# 2014-9-17.net
KiCad netlist of a schematic drawn in Altium Designer
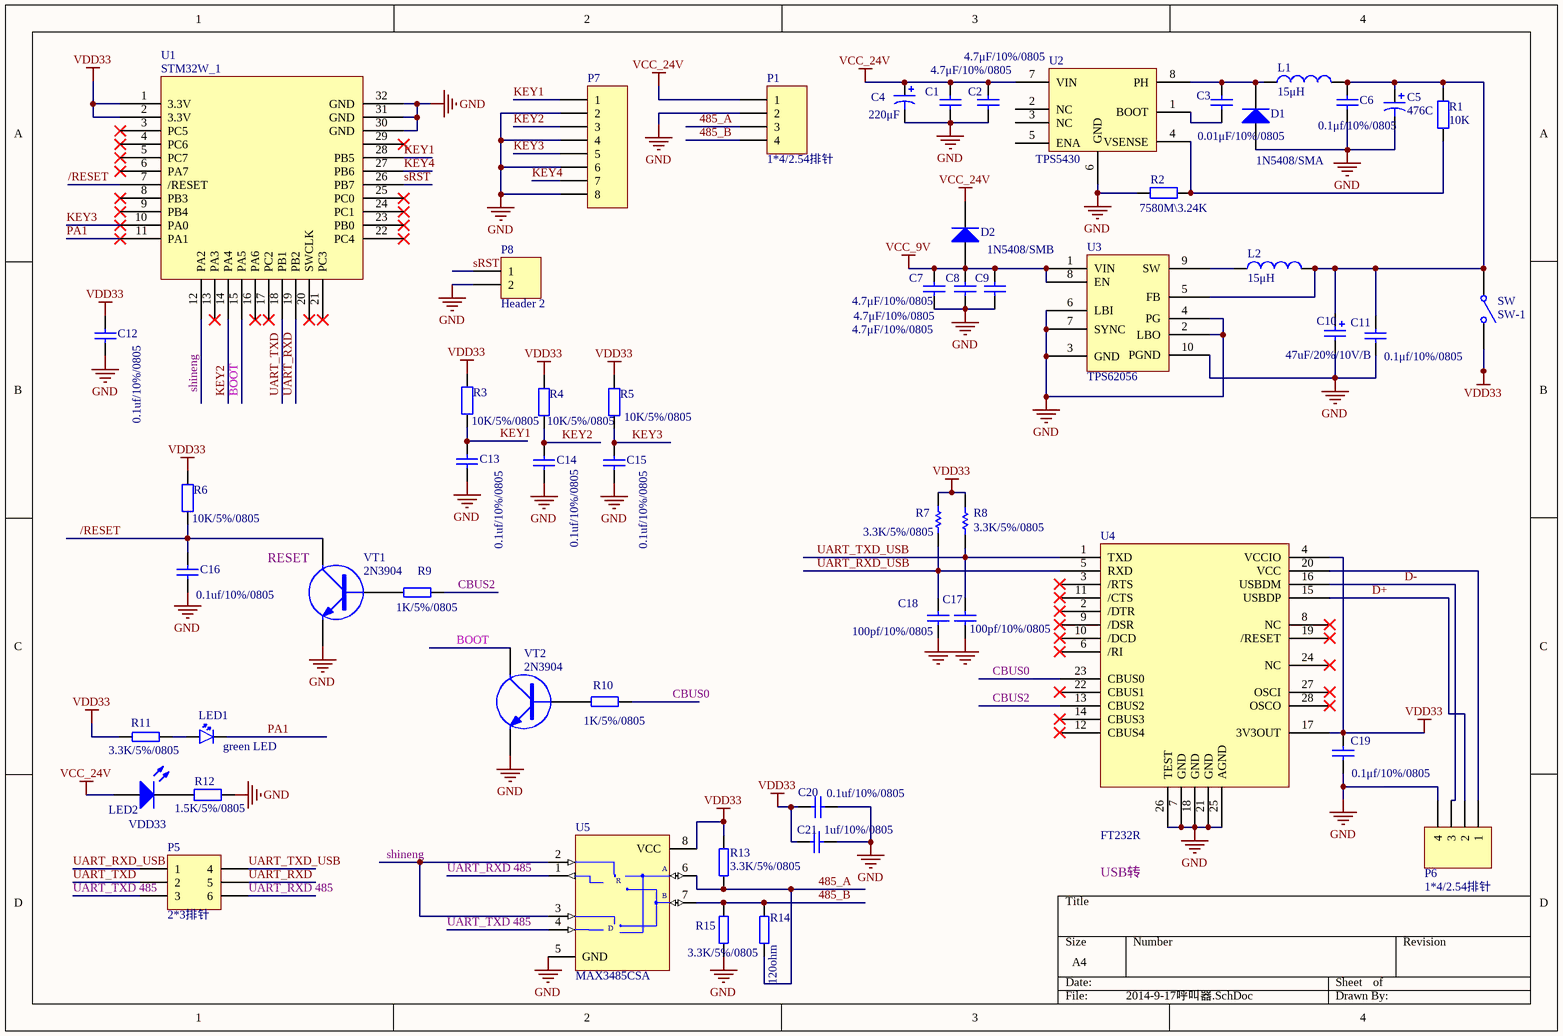
[diagram p0: 2014-9-17呼叫器.SchDoc]

(export (version "E")
  (design (tool "Eeschema 10.0.6"))
  (components
    (comp (ref "C1")
      (value "4.7μF/10%/0805")
      (footprint "C-0805")
      (description "Capacitor")
      (fields (field (name "PUBLISHER") "Altium Limited"))
      (libsource (lib "Miscellaneous Devices") (part "Cap"))
    )
    (comp (ref "C2")
      (value "4.7μF/10%/0805")
      (footprint "C-0805")
      (description "Capacitor")
      (fields (field (name "PUBLISHER") "Altium Limited"))
      (libsource (lib "Miscellaneous Devices") (part "Cap"))
    )
    (comp (ref "C3")
      (value "0.01μF/10%/0805")
      (footprint "C-0805")
      (description "Capacitor")
      (fields (field (name "PUBLISHER") "Altium Limited"))
      (libsource (lib "Miscellaneous Devices") (part "Cap"))
    )
    (comp (ref "C4")
      (value "220μF")
      (footprint "CZ3.0/6.5")
      (description "Polarized Capacitor (Radial)")
      (fields (field (name "PUBLISHER") "Altium Limited"))
      (libsource (lib "Miscellaneous Devices") (part "Cap Pol1"))
    )
    (comp (ref "C5")
      (value "476C")
      (footprint "C-TAN-D")
      (description "Polarized Capacitor (Radial)")
      (fields (field (name "PUBLISHER") "Altium Limited"))
      (libsource (lib "Miscellaneous Devices") (part "Cap Pol1"))
    )
    (comp (ref "C6")
      (value "0.1μf/10%/0805")
      (footprint "C-0805")
      (description "Capacitor")
      (fields (field (name "PUBLISHER") "Altium Limited"))
      (libsource (lib "Miscellaneous Devices") (part "Cap"))
    )
    (comp (ref "C7")
      (value "4.7μF/10%/0805")
      (footprint "C-0805")
      (description "Capacitor")
      (fields (field (name "PUBLISHER") "Altium Limited"))
      (libsource (lib "Miscellaneous Devices") (part "Cap"))
    )
    (comp (ref "C8")
      (value "4.7μF/10%/0805")
      (footprint "C-0805")
      (description "Capacitor")
      (fields (field (name "PUBLISHER") "Altium Limited"))
      (libsource (lib "Miscellaneous Devices") (part "Cap"))
    )
    (comp (ref "C9")
      (value "4.7μF/10%/0805")
      (footprint "C-0805")
      (description "Capacitor")
      (fields (field (name "PUBLISHER") "Altium Limited"))
      (libsource (lib "Miscellaneous Devices") (part "Cap"))
    )
    (comp (ref "C10")
      (value "47uF/20%/10V/B")
      (footprint "C-TAN-B")
      (libsource (lib "浙江关西电机数据库") (part "CAP_polarity"))
    )
    (comp (ref "C11")
      (value "0.1μf/10%/0805")
      (footprint "C-0805")
      (description "Capacitor")
      (fields (field (name "PUBLISHER") "Altium Limited"))
      (libsource (lib "Miscellaneous Devices") (part "Cap"))
    )
    (comp (ref "C12")
      (value "0.1uf/10%/0805")
      (footprint "C-0805")
      (description "Capacitor")
      (fields (field (name "PUBLISHER") "Altium Limited"))
      (libsource (lib "Miscellaneous Devices") (part "Cap"))
    )
    (comp (ref "C13")
      (value "0.1uf/10%/0805")
      (footprint "C-0805")
      (description "Capacitor")
      (fields (field (name "PUBLISHER") "Altium Limited"))
      (libsource (lib "Miscellaneous Devices") (part "Cap"))
    )
    (comp (ref "C14")
      (value "0.1uf/10%/0805")
      (footprint "C-0805")
      (description "Capacitor")
      (fields (field (name "PUBLISHER") "Altium Limited"))
      (libsource (lib "Miscellaneous Devices") (part "Cap"))
    )
    (comp (ref "C15")
      (value "0.1uf/10%/0805")
      (footprint "C-0805")
      (description "Capacitor")
      (fields (field (name "PUBLISHER") "Altium Limited"))
      (libsource (lib "Miscellaneous Devices") (part "Cap"))
    )
    (comp (ref "C16")
      (value "0.1uf/10%/0805")
      (footprint "C-0805")
      (description "Capacitor")
      (fields (field (name "PUBLISHER") "Altium Limited"))
      (libsource (lib "Miscellaneous Devices") (part "Cap"))
    )
    (comp (ref "C17")
      (value "100pf/10%/0805")
      (footprint "C-0805")
      (description "Capacitor")
      (fields (field (name "PUBLISHER") "Altium Limited"))
      (libsource (lib "Miscellaneous Devices") (part "Cap"))
    )
    (comp (ref "C18")
      (value "100pf/10%/0805")
      (footprint "C-0805")
      (description "Capacitor")
      (fields (field (name "PUBLISHER") "Altium Limited"))
      (libsource (lib "Miscellaneous Devices") (part "Cap"))
    )
    (comp (ref "C19")
      (value "0.1μf/10%/0805")
      (footprint "C-0805")
      (description "Capacitor")
      (fields (field (name "PUBLISHER") "Altium Limited"))
      (libsource (lib "Miscellaneous Devices") (part "Cap"))
    )
    (comp (ref "C20")
      (value "0.1uf/10%/0805")
      (footprint "C-0805")
      (description "Capacitor")
      (fields (field (name "PUBLISHER") "Altium Limited"))
      (libsource (lib "Miscellaneous Devices") (part "Cap"))
    )
    (comp (ref "C21")
      (value "1uf/10%/0805")
      (footprint "C-0805")
      (description "Capacitor")
      (fields (field (name "PUBLISHER") "Altium Limited"))
      (libsource (lib "Miscellaneous Devices") (part "Cap"))
    )
    (comp (ref "D1")
      (value "1N5408/SMA")
      (footprint "SMA 2+")
      (description "3 Amp Medium Power Silicon Rectifier Diode")
      (fields (field (name "PUBLISHER") "Altium Limited"))
      (libsource (lib "Miscellaneous Devices") (part "Diode 1N5408"))
    )
    (comp (ref "D2")
      (value "1N5408/SMB")
      (footprint "smb")
      (description "3 Amp Medium Power Silicon Rectifier Diode")
      (fields (field (name "PUBLISHER") "Altium Limited"))
      (libsource (lib "Miscellaneous Devices") (part "Diode 1N5408"))
    )
    (comp (ref "L1")
      (value "15μH")
      (footprint "GSDS104C2")
      (description "Inductor")
      (fields (field (name "PUBLISHER") "Altium Limited"))
      (libsource (lib "Miscellaneous Devices") (part "Inductor"))
    )
    (comp (ref "L2")
      (value "15μH")
      (footprint "GSDS104C2")
      (description "Inductor")
      (fields (field (name "PUBLISHER") "Altium Limited"))
      (libsource (lib "Miscellaneous Devices") (part "Inductor"))
    )
    (comp (ref "LED1") (value "green LED") (footprint "LED-φ3") (libsource (lib "Haze") (part "LED")))
    (comp (ref "LED2")
      (value "VDD33")
      (footprint "LED-φ3")
      (description "Typical BLUE SiC LED")
      (fields (field (name "PUBLISHER") "Altium Limited"))
      (libsource (lib "Miscellaneous Devices") (part "LED3"))
    )
    (comp (ref "P1")
      (value "1*4/2.54排针")
      (footprint "PIN-S-2.54-1*4")
      (description "Header, 4-Pin")
      (fields (field (name "PUBLISHER") "Altium Limited"))
      (libsource (lib "") (part "Header 4_1"))
    )
    (comp (ref "P5")
      (value "2*3排针")
      (footprint "HDR2X3_CEN")
      (description "Header, 3-Pin, Dual row")
      (fields (field (name "PUBLISHER") "Altium Limited"))
      (libsource (lib "Miscellaneous Connectors") (part "Header 3X2A"))
    )
    (comp (ref "P6")
      (value "1*4/2.54排针")
      (footprint "PIN-S-2.54-1*4")
      (description "Header, 4-Pin")
      (fields (field (name "PUBLISHER") "Altium Limited"))
      (libsource (lib "Miscellaneous Connectors") (part "Header 4"))
    )
    (comp (ref "P7")
      (value "Header 8")
      (footprint "HDR1X8")
      (description "Header, 8-Pin")
      (fields (field (name "PUBLISHER") "Altium Limited"))
      (libsource (lib "Miscellaneous Connectors") (part "Header 8"))
    )
    (comp (ref "P8")
      (value "Header 2")
      (footprint "HDR1X2")
      (description "Header, 2-Pin")
      (fields (field (name "PUBLISHER") "Altium Limited"))
      (libsource (lib "Miscellaneous Connectors") (part "Header 2"))
    )
    (comp (ref "R1")
      (value "10K")
      (footprint "R-0805")
      (description "Resistor")
      (fields (field (name "PUBLISHER") "Altium Limited"))
      (libsource (lib "Miscellaneous Devices") (part "Res2"))
    )
    (comp (ref "R2")
      (value "7580~{M}3.24K")
      (footprint "R-0805")
      (description "Resistor")
      (fields (field (name "PUBLISHER") "Altium Limited"))
      (libsource (lib "") (part "Res2_1"))
    )
    (comp (ref "R3")
      (value "10K/5%/0805")
      (footprint "R-0805")
      (description "Resistor")
      (fields (field (name "PUBLISHER") "Altium Limited"))
      (libsource (lib "Miscellaneous Devices") (part "Res2"))
    )
    (comp (ref "R4")
      (value "10K/5%/0805")
      (footprint "R-0805")
      (description "Resistor")
      (fields (field (name "PUBLISHER") "Altium Limited"))
      (libsource (lib "Miscellaneous Devices") (part "Res2"))
    )
    (comp (ref "R5")
      (value "10K/5%/0805")
      (footprint "R-0805")
      (description "Resistor")
      (fields (field (name "PUBLISHER") "Altium Limited"))
      (libsource (lib "Miscellaneous Devices") (part "Res2"))
    )
    (comp (ref "R6")
      (value "10K/5%/0805")
      (footprint "R-0805")
      (description "Resistor")
      (fields (field (name "PUBLISHER") "Altium Limited"))
      (libsource (lib "Miscellaneous Devices") (part "Res2"))
    )
    (comp (ref "R7")
      (value "3.3K/5%/0805")
      (footprint "R-0805")
      (libsource (lib "SCHLIBRARIES") (part "RES_1"))
    )
    (comp (ref "R8")
      (value "3.3K/5%/0805")
      (footprint "R-0805")
      (libsource (lib "SCHLIBRARIES") (part "RES_1"))
    )
    (comp (ref "R9")
      (value "1K/5%/0805")
      (footprint "R-0805")
      (description "R")
      (libsource (lib "Haze") (part "RES"))
    )
    (comp (ref "R10")
      (value "1K/5%/0805")
      (footprint "R-0805")
      (description "R")
      (libsource (lib "Haze") (part "RES"))
    )
    (comp (ref "R11")
      (value "3.3K/5%/0805")
      (footprint "R-0805")
      (description "R")
      (libsource (lib "Haze") (part "RES"))
    )
    (comp (ref "R12")
      (value "1.5K/5%/0805")
      (footprint "R-0805")
      (description "Resistor")
      (fields (field (name "PUBLISHER") "Altium Limited"))
      (libsource (lib "") (part "Res2_1"))
    )
    (comp (ref "R13")
      (value "3.3K/5%/0805")
      (footprint "R-0805")
      (description "R")
      (libsource (lib "Haze") (part "RES"))
    )
    (comp (ref "R14")
      (value "120ohm")
      (footprint "R-0805")
      (description "R")
      (libsource (lib "Haze") (part "RES"))
    )
    (comp (ref "R15")
      (value "3.3K/5%/0805")
      (footprint "R-0805")
      (description "R")
      (libsource (lib "Haze") (part "RES"))
    )
    (comp (ref "SW")
      (value "SW-1")
      (footprint "PIN-S-2.54-1*2")
      (libsource (lib "SCHLIBRARIES") (part "SW-1"))
    )
    (comp (ref "U1")
      (value "STM32W_1")
      (footprint "STM32W108-3")
      (libsource (lib "STM32W108-3") (part "STM32W108-3"))
    )
    (comp (ref "U2") (value "TPS5430") (footprint "SO-G8") (libsource (lib "SCHLIBRARIES") (part "TPS5430")))
    (comp (ref "U3")
      (value "TPS62056")
      (footprint "MSOP-10")
      (libsource (lib "SCHLIBRARIES") (part "TPS62056"))
    )
    (comp (ref "U4") (value "FT232R") (footprint "SSOP-28") (libsource (lib "Haze") (part "FT232R")))
    (comp (ref "U5")
      (value "MAX3485CSA")
      (footprint "SO-G8")
      (description "Low-Power, Slew-Rate-Limited RS-485/RS-422 Transceiver")
      (fields (field (name "PUBLISHER") "Altium Limited"))
      (libsource (lib "Maxim Communication Transceiver") (part "MAX485CSA"))
    )
    (comp (ref "VT1")
      (value "2N3904")
      (footprint "SOT23-3")
      (description "NPN Transistor")
      (libsource (lib "Haze") (part "NPN"))
    )
    (comp (ref "VT2")
      (value "2N3904")
      (footprint "SOT23-3")
      (description "NPN Transistor")
      (libsource (lib "Haze") (part "NPN"))
    )
  )
  (nets
    (net (code "1") (name "/485_A") (class "Default")
      (node (ref "P1") (pin "3") (pinfunction "3_3") (pintype "passive"))
      (node (ref "R13") (pin "1") (pinfunction "1_1") (pintype "passive"))
      (node (ref "R14") (pin "2") (pinfunction "2_2") (pintype "passive"))
      (node (ref "U5") (pin "6") (pinfunction "A_6") (pintype "bidirectional"))
    )
    (net (code "2") (name "/485_B") (class "Default")
      (node (ref "P1") (pin "4") (pinfunction "4_4") (pintype "passive"))
      (node (ref "R14") (pin "1") (pinfunction "1_1") (pintype "passive"))
      (node (ref "R15") (pin "2") (pinfunction "2_2") (pintype "passive"))
      (node (ref "U5") (pin "7") (pinfunction "B_7") (pintype "bidirectional"))
    )
    (net (code "3") (name "/BOOT") (class "Default")
      (node (ref "U1") (pin "15") (pinfunction "PA5_15") (pintype "passive"))
      (node (ref "VT2") (pin "3") (pinfunction "C_3") (pintype "passive"))
    )
    (net (code "4") (name "/CBUS0") (class "Default")
      (node (ref "R10") (pin "2") (pinfunction "2_2") (pintype "passive"))
      (node (ref "U4") (pin "23") (pinfunction "CBUS0_23") (pintype "passive"))
    )
    (net (code "5") (name "/CBUS2") (class "Default")
      (node (ref "R9") (pin "2") (pinfunction "2_2") (pintype "passive"))
      (node (ref "U4") (pin "13") (pinfunction "CBUS2_13") (pintype "passive"))
    )
    (net (code "6") (name "/D+") (class "Default")
      (node (ref "P6") (pin "2") (pinfunction "2_2") (pintype "passive"))
      (node (ref "U4") (pin "15") (pinfunction "USBDP_15") (pintype "passive"))
    )
    (net (code "7") (name "/D-") (class "Default")
      (node (ref "P6") (pin "3") (pinfunction "3_3") (pintype "passive"))
      (node (ref "U4") (pin "16") (pinfunction "USBDM_16") (pintype "passive"))
    )
    (net (code "8") (name "/KEY1") (class "Default")
      (node (ref "C13") (pin "2") (pinfunction "2_2") (pintype "passive"))
      (node (ref "P7") (pin "1") (pinfunction "1_1") (pintype "passive"))
      (node (ref "R3") (pin "1") (pinfunction "1_1") (pintype "passive"))
      (node (ref "U1") (pin "28") (pinfunction "PB5_28") (pintype "passive"))
    )
    (net (code "9") (name "/KEY2") (class "Default")
      (node (ref "C14") (pin "2") (pinfunction "2_2") (pintype "passive"))
      (node (ref "P7") (pin "3") (pinfunction "3_3") (pintype "passive"))
      (node (ref "R4") (pin "1") (pinfunction "1_1") (pintype "passive"))
      (node (ref "U1") (pin "14") (pinfunction "PA4_14") (pintype "passive"))
    )
    (net (code "10") (name "/KEY3") (class "Default")
      (node (ref "C15") (pin "2") (pinfunction "2_2") (pintype "passive"))
      (node (ref "P7") (pin "5") (pinfunction "5_5") (pintype "passive"))
      (node (ref "R5") (pin "1") (pinfunction "1_1") (pintype "passive"))
      (node (ref "U1") (pin "10") (pinfunction "PA0_10") (pintype "passive"))
    )
    (net (code "11") (name "/KEY4") (class "Default")
      (node (ref "P7") (pin "7") (pinfunction "7_7") (pintype "passive"))
      (node (ref "U1") (pin "27") (pinfunction "PB6_27") (pintype "passive"))
    )
    (net (code "12") (name "/PA1") (class "Default")
      (node (ref "LED1") (pin "2") (pinfunction "K_2") (pintype "passive"))
      (node (ref "U1") (pin "11") (pinfunction "PA1_11") (pintype "passive"))
    )
    (net (code "13") (name "/UART_RXD") (class "Default")
      (node (ref "P5") (pin "5") (pinfunction "5_5") (pintype "passive"))
      (node (ref "U1") (pin "19") (pinfunction "PB2_19") (pintype "passive"))
    )
    (net (code "14") (name "/UART_RXD 485") (class "Default")
      (node (ref "P5") (pin "6") (pinfunction "6_6") (pintype "passive"))
      (node (ref "U5") (pin "1") (pinfunction "RO_1") (pintype "output"))
    )
    (net (code "15") (name "/UART_RXD_USB") (class "Default")
      (node (ref "C18") (pin "2") (pinfunction "2_2") (pintype "passive"))
      (node (ref "P5") (pin "1") (pinfunction "1_1") (pintype "passive"))
      (node (ref "R7") (pin "1") (pinfunction "1_1") (pintype "passive"))
      (node (ref "U4") (pin "5") (pinfunction "RXD_5") (pintype "passive"))
    )
    (net (code "16") (name "/UART_TXD") (class "Default")
      (node (ref "P5") (pin "2") (pinfunction "2_2") (pintype "passive"))
      (node (ref "U1") (pin "18") (pinfunction "PB1_18") (pintype "passive"))
    )
    (net (code "17") (name "/UART_TXD 485") (class "Default")
      (node (ref "P5") (pin "3") (pinfunction "3_3") (pintype "passive"))
      (node (ref "U5") (pin "4") (pinfunction "DI_4") (pintype "input"))
    )
    (net (code "18") (name "/UART_TXD_USB") (class "Default")
      (node (ref "C17") (pin "2") (pinfunction "2_2") (pintype "passive"))
      (node (ref "P5") (pin "4") (pinfunction "4_4") (pintype "passive"))
      (node (ref "R8") (pin "1") (pinfunction "1_1") (pintype "passive"))
      (node (ref "U4") (pin "1") (pinfunction "TXD_1") (pintype "passive"))
    )
    (net (code "19") (name "/sRST") (class "Default")
      (node (ref "P8") (pin "1") (pinfunction "1_1") (pintype "passive"))
      (node (ref "U1") (pin "26") (pinfunction "PB7_26") (pintype "passive"))
    )
    (net (code "20") (name "/shineng") (class "Default")
      (node (ref "U1") (pin "12") (pinfunction "PA2_12") (pintype "passive"))
      (node (ref "U5") (pin "2") (pinfunction "~{RE}_2") (pintype "input"))
      (node (ref "U5") (pin "3") (pinfunction "DE_3") (pintype "input"))
    )
    (net (code "21") (name "/{slash}RESET") (class "Default")
      (node (ref "C16") (pin "2") (pinfunction "2_2") (pintype "passive"))
      (node (ref "R6") (pin "1") (pinfunction "1_1") (pintype "passive"))
      (node (ref "U1") (pin "7") (pinfunction "/RESET_7") (pintype "passive"))
      (node (ref "VT1") (pin "3") (pinfunction "C_3") (pintype "passive"))
    )
    (net (code "22") (name "GND") (class "Default")
      (node (ref "C1") (pin "1") (pinfunction "1_1") (pintype "passive"))
      (node (ref "C10") (pin "2") (pinfunction "2_2") (pintype "passive"))
      (node (ref "C11") (pin "1") (pinfunction "1_1") (pintype "passive"))
      (node (ref "C12") (pin "1") (pinfunction "1_1") (pintype "passive"))
      (node (ref "C13") (pin "1") (pinfunction "1_1") (pintype "passive"))
      (node (ref "C14") (pin "1") (pinfunction "1_1") (pintype "passive"))
      (node (ref "C15") (pin "1") (pinfunction "1_1") (pintype "passive"))
      (node (ref "C16") (pin "1") (pinfunction "1_1") (pintype "passive"))
      (node (ref "C17") (pin "1") (pinfunction "1_1") (pintype "passive"))
      (node (ref "C18") (pin "1") (pinfunction "1_1") (pintype "passive"))
      (node (ref "C19") (pin "1") (pinfunction "1_1") (pintype "passive"))
      (node (ref "C2") (pin "1") (pinfunction "1_1") (pintype "passive"))
      (node (ref "C20") (pin "1") (pinfunction "1_1") (pintype "passive"))
      (node (ref "C21") (pin "1") (pinfunction "1_1") (pintype "passive"))
      (node (ref "C4") (pin "2") (pinfunction "2_2") (pintype "passive"))
      (node (ref "C5") (pin "2") (pinfunction "2_2") (pintype "passive"))
      (node (ref "C6") (pin "1") (pinfunction "1_1") (pintype "passive"))
      (node (ref "C7") (pin "1") (pinfunction "1_1") (pintype "passive"))
      (node (ref "C8") (pin "1") (pinfunction "1_1") (pintype "passive"))
      (node (ref "C9") (pin "1") (pinfunction "1_1") (pintype "passive"))
      (node (ref "D1") (pin "1") (pinfunction "A_1") (pintype "passive"))
      (node (ref "P1") (pin "2") (pinfunction "2_2") (pintype "passive"))
      (node (ref "P6") (pin "4") (pinfunction "4_4") (pintype "passive"))
      (node (ref "P7") (pin "2") (pinfunction "2_2") (pintype "passive"))
      (node (ref "P7") (pin "4") (pinfunction "4_4") (pintype "passive"))
      (node (ref "P7") (pin "6") (pinfunction "6_6") (pintype "passive"))
      (node (ref "P7") (pin "8") (pinfunction "8_8") (pintype "passive"))
      (node (ref "P8") (pin "2") (pinfunction "2_2") (pintype "passive"))
      (node (ref "R12") (pin "1") (pinfunction "1_1") (pintype "passive"))
      (node (ref "R15") (pin "1") (pinfunction "1_1") (pintype "passive"))
      (node (ref "R2") (pin "2") (pinfunction "2_2") (pintype "passive"))
      (node (ref "U1") (pin "30") (pinfunction "GND_30") (pintype "passive"))
      (node (ref "U1") (pin "31") (pinfunction "GND_31") (pintype "passive"))
      (node (ref "U1") (pin "32") (pinfunction "GND_32") (pintype "passive"))
      (node (ref "U2") (pin "6") (pinfunction "GND_6") (pintype "passive"))
      (node (ref "U3") (pin "10") (pinfunction "PGND_10") (pintype "passive"))
      (node (ref "U3") (pin "2") (pinfunction "LBO_2") (pintype "passive"))
      (node (ref "U3") (pin "3") (pinfunction "GND_3") (pintype "passive"))
      (node (ref "U3") (pin "4") (pinfunction "PG_4") (pintype "passive"))
      (node (ref "U3") (pin "6") (pinfunction "LBI_6") (pintype "passive"))
      (node (ref "U3") (pin "7") (pinfunction "SYNC_7") (pintype "passive"))
      (node (ref "U4") (pin "18") (pinfunction "GND_18") (pintype "passive"))
      (node (ref "U4") (pin "21") (pinfunction "GND_21") (pintype "passive"))
      (node (ref "U4") (pin "25") (pinfunction "AGND_25") (pintype "passive"))
      (node (ref "U4") (pin "26") (pinfunction "TEST_26") (pintype "passive"))
      (node (ref "U4") (pin "7") (pinfunction "GND_7") (pintype "passive"))
      (node (ref "U5") (pin "5") (pinfunction "GND_5") (pintype "power_in"))
      (node (ref "VT1") (pin "2") (pinfunction "E_2") (pintype "passive"))
      (node (ref "VT2") (pin "2") (pinfunction "E_2") (pintype "passive"))
    )
    (net (code "23") (name "Net-(D1-K)") (class "Default")
      (node (ref "C3") (pin "2") (pinfunction "2_2") (pintype "passive"))
      (node (ref "D1") (pin "2") (pinfunction "K_2") (pintype "passive"))
      (node (ref "L1") (pin "1") (pinfunction "1_1") (pintype "passive"))
      (node (ref "U2") (pin "8") (pinfunction "PH_8") (pintype "passive"))
    )
    (net (code "24") (name "Net-(LED1-A)") (class "Default")
      (node (ref "LED1") (pin "1") (pinfunction "A_1") (pintype "passive"))
      (node (ref "R11") (pin "2") (pinfunction "2_2") (pintype "passive"))
    )
    (net (code "25") (name "Net-(LED2-K)") (class "Default")
      (node (ref "LED2") (pin "2") (pinfunction "K_2") (pintype "passive"))
      (node (ref "R12") (pin "2") (pinfunction "2_2") (pintype "passive"))
    )
    (net (code "26") (name "Net-(U2-BOOT)") (class "Default")
      (node (ref "C3") (pin "1") (pinfunction "1_1") (pintype "passive"))
      (node (ref "U2") (pin "1") (pinfunction "BOOT_1") (pintype "passive"))
    )
    (net (code "27") (name "Net-(U2-VSENSE)") (class "Default")
      (node (ref "R1") (pin "1") (pinfunction "1_1") (pintype "passive"))
      (node (ref "R2") (pin "1") (pinfunction "1_1") (pintype "passive"))
      (node (ref "U2") (pin "4") (pinfunction "VSENSE_4") (pintype "passive"))
    )
    (net (code "28") (name "Net-(U3-FB)") (class "Default")
      (node (ref "C10") (pin "1") (pinfunction "1_1") (pintype "passive"))
      (node (ref "C11") (pin "2") (pinfunction "2_2") (pintype "passive"))
      (node (ref "C5") (pin "1") (pinfunction "1_1") (pintype "passive"))
      (node (ref "C6") (pin "2") (pinfunction "2_2") (pintype "passive"))
      (node (ref "L1") (pin "2") (pinfunction "2_2") (pintype "passive"))
      (node (ref "L2") (pin "2") (pinfunction "2_2") (pintype "passive"))
      (node (ref "R1") (pin "2") (pinfunction "2_2") (pintype "passive"))
      (node (ref "SW") (pin "1") (pinfunction "1_1") (pintype "passive"))
      (node (ref "U3") (pin "5") (pinfunction "FB_5") (pintype "passive"))
    )
    (net (code "29") (name "Net-(U3-SW)") (class "Default")
      (node (ref "L2") (pin "1") (pinfunction "1_1") (pintype "passive"))
      (node (ref "U3") (pin "9") (pinfunction "SW_9") (pintype "passive"))
    )
    (net (code "30") (name "Net-(U4-VCC)") (class "Default")
      (node (ref "P6") (pin "1") (pinfunction "1_1") (pintype "passive"))
      (node (ref "U4") (pin "20") (pinfunction "VCC_20") (pintype "passive"))
    )
    (net (code "31") (name "Net-(VT1-B)") (class "Default")
      (node (ref "R9") (pin "1") (pinfunction "1_1") (pintype "passive"))
      (node (ref "VT1") (pin "1") (pinfunction "B_1") (pintype "passive"))
    )
    (net (code "32") (name "Net-(VT2-B)") (class "Default")
      (node (ref "R10") (pin "1") (pinfunction "1_1") (pintype "passive"))
      (node (ref "VT2") (pin "1") (pinfunction "B_1") (pintype "passive"))
    )
    (net (code "33") (name "VCC_9V") (class "Default")
      (node (ref "C7") (pin "2") (pinfunction "2_2") (pintype "passive"))
      (node (ref "C8") (pin "2") (pinfunction "2_2") (pintype "passive"))
      (node (ref "C9") (pin "2") (pinfunction "2_2") (pintype "passive"))
      (node (ref "D2") (pin "1") (pinfunction "A_1") (pintype "passive"))
      (node (ref "U3") (pin "1") (pinfunction "VIN_1") (pintype "passive"))
      (node (ref "U3") (pin "8") (pinfunction "EN_8") (pintype "passive"))
    )
    (net (code "34") (name "VCC_24V") (class "Default")
      (node (ref "C1") (pin "2") (pinfunction "2_2") (pintype "passive"))
      (node (ref "C2") (pin "2") (pinfunction "2_2") (pintype "passive"))
      (node (ref "C4") (pin "1") (pinfunction "1_1") (pintype "passive"))
      (node (ref "D2") (pin "2") (pinfunction "K_2") (pintype "passive"))
      (node (ref "LED2") (pin "1") (pinfunction "A_1") (pintype "passive"))
      (node (ref "P1") (pin "1") (pinfunction "1_1") (pintype "passive"))
      (node (ref "U2") (pin "7") (pinfunction "VIN_7") (pintype "passive"))
    )
    (net (code "35") (name "VDD33") (class "Default")
      (node (ref "C12") (pin "2") (pinfunction "2_2") (pintype "passive"))
      (node (ref "C19") (pin "2") (pinfunction "2_2") (pintype "passive"))
      (node (ref "C20") (pin "2") (pinfunction "2_2") (pintype "passive"))
      (node (ref "C21") (pin "2") (pinfunction "2_2") (pintype "passive"))
      (node (ref "R11") (pin "1") (pinfunction "1_1") (pintype "passive"))
      (node (ref "R13") (pin "2") (pinfunction "2_2") (pintype "passive"))
      (node (ref "R3") (pin "2") (pinfunction "2_2") (pintype "passive"))
      (node (ref "R4") (pin "2") (pinfunction "2_2") (pintype "passive"))
      (node (ref "R5") (pin "2") (pinfunction "2_2") (pintype "passive"))
      (node (ref "R6") (pin "2") (pinfunction "2_2") (pintype "passive"))
      (node (ref "R7") (pin "2") (pinfunction "2_2") (pintype "passive"))
      (node (ref "R8") (pin "2") (pinfunction "2_2") (pintype "passive"))
      (node (ref "SW") (pin "2") (pinfunction "2_2") (pintype "passive"))
      (node (ref "U1") (pin "1") (pinfunction "3.3V_1") (pintype "passive"))
      (node (ref "U1") (pin "2") (pinfunction "3.3V_2") (pintype "passive"))
      (node (ref "U4") (pin "17") (pinfunction "3V3OUT_17") (pintype "passive"))
      (node (ref "U4") (pin "4") (pinfunction "VCCIO_4") (pintype "passive"))
      (node (ref "U5") (pin "8") (pinfunction "VCC_8") (pintype "power_in"))
    )
    (net (code "36") (name "unconnected-(U1-PA3-Pad13)") (class "Default")
      (node (ref "U1") (pin "13") (pinfunction "PA3_13") (pintype "passive+no_connect"))
    )
    (net (code "37") (name "unconnected-(U1-PA6-Pad16)") (class "Default")
      (node (ref "U1") (pin "16") (pinfunction "PA6_16") (pintype "passive+no_connect"))
    )
    (net (code "38") (name "unconnected-(U1-PA7-Pad6)") (class "Default")
      (node (ref "U1") (pin "6") (pinfunction "PA7_6") (pintype "passive+no_connect"))
    )
    (net (code "39") (name "unconnected-(U1-PB0-Pad23)") (class "Default")
      (node (ref "U1") (pin "23") (pinfunction "PB0_23") (pintype "passive+no_connect"))
    )
    (net (code "40") (name "unconnected-(U1-PB3-Pad8)") (class "Default")
      (node (ref "U1") (pin "8") (pinfunction "PB3_8") (pintype "passive+no_connect"))
    )
    (net (code "41") (name "unconnected-(U1-PB4-Pad9)") (class "Default")
      (node (ref "U1") (pin "9") (pinfunction "PB4_9") (pintype "passive+no_connect"))
    )
    (net (code "42") (name "unconnected-(U1-PC0-Pad25)") (class "Default")
      (node (ref "U1") (pin "25") (pinfunction "PC0_25") (pintype "passive+no_connect"))
    )
    (net (code "43") (name "unconnected-(U1-PC1-Pad24)") (class "Default")
      (node (ref "U1") (pin "24") (pinfunction "PC1_24") (pintype "passive+no_connect"))
    )
    (net (code "44") (name "unconnected-(U1-PC2-Pad17)") (class "Default")
      (node (ref "U1") (pin "17") (pinfunction "PC2_17") (pintype "passive+no_connect"))
    )
    (net (code "45") (name "unconnected-(U1-PC3-Pad21)") (class "Default")
      (node (ref "U1") (pin "21") (pinfunction "PC3_21") (pintype "passive+no_connect"))
    )
    (net (code "46") (name "unconnected-(U1-PC4-Pad22)") (class "Default")
      (node (ref "U1") (pin "22") (pinfunction "PC4_22") (pintype "passive+no_connect"))
    )
    (net (code "47") (name "unconnected-(U1-PC5-Pad3)") (class "Default")
      (node (ref "U1") (pin "3") (pinfunction "PC5_3") (pintype "passive+no_connect"))
    )
    (net (code "48") (name "unconnected-(U1-PC6-Pad4)") (class "Default")
      (node (ref "U1") (pin "4") (pinfunction "PC6_4") (pintype "passive+no_connect"))
    )
    (net (code "49") (name "unconnected-(U1-PC7-Pad5)") (class "Default")
      (node (ref "U1") (pin "5") (pinfunction "PC7_5") (pintype "passive+no_connect"))
    )
    (net (code "50") (name "unconnected-(U1-Pad29)") (class "Default")
      (node (ref "U1") (pin "29") (pintype "passive+no_connect"))
    )
    (net (code "51") (name "unconnected-(U1-SWCLK-Pad20)") (class "Default")
      (node (ref "U1") (pin "20") (pinfunction "SWCLK_20") (pintype "passive+no_connect"))
    )
    (net (code "52") (name "unconnected-(U2-ENA-Pad5)") (class "Default")
      (node (ref "U2") (pin "5") (pinfunction "ENA_5") (pintype "passive"))
    )
    (net (code "53") (name "unconnected-(U2-NC-Pad2)") (class "Default")
      (node (ref "U2") (pin "2") (pinfunction "NC_2") (pintype "passive"))
    )
    (net (code "54") (name "unconnected-(U2-NC-Pad3)") (class "Default")
      (node (ref "U2") (pin "3") (pinfunction "NC_3") (pintype "passive"))
    )
    (net (code "55") (name "unconnected-(U4-CBUS1-Pad22)") (class "Default")
      (node (ref "U4") (pin "22") (pinfunction "CBUS1_22") (pintype "passive+no_connect"))
    )
    (net (code "56") (name "unconnected-(U4-CBUS3-Pad14)") (class "Default")
      (node (ref "U4") (pin "14") (pinfunction "CBUS3_14") (pintype "passive+no_connect"))
    )
    (net (code "57") (name "unconnected-(U4-CBUS4-Pad12)") (class "Default")
      (node (ref "U4") (pin "12") (pinfunction "CBUS4_12") (pintype "passive+no_connect"))
    )
    (net (code "58") (name "unconnected-(U4-NC-Pad8)") (class "Default")
      (node (ref "U4") (pin "8") (pinfunction "NC_8") (pintype "passive+no_connect"))
    )
    (net (code "59") (name "unconnected-(U4-NC-Pad24)") (class "Default")
      (node (ref "U4") (pin "24") (pinfunction "NC_24") (pintype "passive+no_connect"))
    )
    (net (code "60") (name "unconnected-(U4-OSCI-Pad27)") (class "Default")
      (node (ref "U4") (pin "27") (pinfunction "OSCI_27") (pintype "passive+no_connect"))
    )
    (net (code "61") (name "unconnected-(U4-OSCO-Pad28)") (class "Default")
      (node (ref "U4") (pin "28") (pinfunction "OSCO_28") (pintype "passive+no_connect"))
    )
    (net (code "62") (name "unconnected-(U4-{slash}CTS-Pad11)") (class "Default")
      (node (ref "U4") (pin "11") (pinfunction "/CTS_11") (pintype "passive+no_connect"))
    )
    (net (code "63") (name "unconnected-(U4-{slash}DCD-Pad10)") (class "Default")
      (node (ref "U4") (pin "10") (pinfunction "/DCD_10") (pintype "passive+no_connect"))
    )
    (net (code "64") (name "unconnected-(U4-{slash}DSR-Pad9)") (class "Default")
      (node (ref "U4") (pin "9") (pinfunction "/DSR_9") (pintype "passive+no_connect"))
    )
    (net (code "65") (name "unconnected-(U4-{slash}DTR-Pad2)") (class "Default")
      (node (ref "U4") (pin "2") (pinfunction "/DTR_2") (pintype "passive+no_connect"))
    )
    (net (code "66") (name "unconnected-(U4-{slash}RESET-Pad19)") (class "Default")
      (node (ref "U4") (pin "19") (pinfunction "/RESET_19") (pintype "passive+no_connect"))
    )
    (net (code "67") (name "unconnected-(U4-{slash}RI-Pad6)") (class "Default")
      (node (ref "U4") (pin "6") (pinfunction "/RI_6") (pintype "passive+no_connect"))
    )
    (net (code "68") (name "unconnected-(U4-{slash}RTS-Pad3)") (class "Default")
      (node (ref "U4") (pin "3") (pinfunction "/RTS_3") (pintype "passive+no_connect"))
    )
  )
)
